# Safety_2019_V_3_0_Connectors.net
KiCad netlist of a schematic drawn in Altium Designer
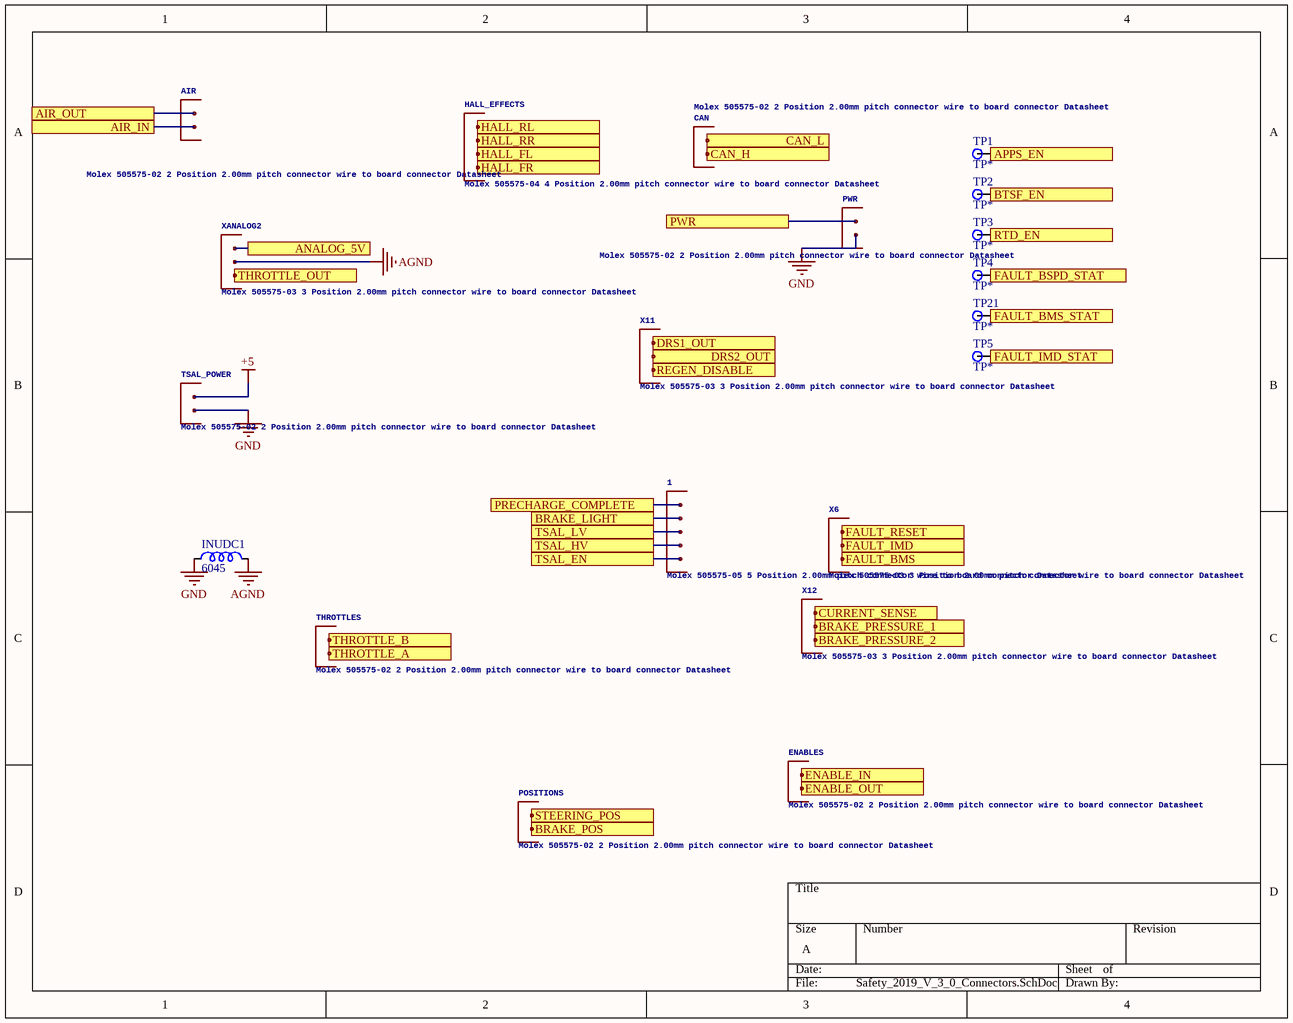
[diagram p0: Safety_2019_V_3_0_Connectors.SchDoc]

(export (version "E")
  (design (tool "Eeschema 10.0.6"))
  (components
    (comp (ref "1")
      (value "Molex 505575-05 5 Position 2.00mm pitch connector wire to board connector Datasheet")
      (footprint "505575-05")
      (fields (field (name "LIBRARYNAME") "MOLEX Micro-Lock"))
      (libsource (lib "MOLEX Micro-Lock") (part "505575-05"))
    )
    (comp (ref "AIR")
      (value "Molex 505575-02 2 Position 2.00mm pitch connector wire to board connector Datasheet")
      (footprint "505575-02")
      (fields (field (name "LIBRARYNAME") "MOLEX Micro-Lock"))
      (libsource (lib "MOLEX Micro-Lock") (part "505575-02"))
    )
    (comp (ref "CAN")
      (value "Molex 505575-02 2 Position 2.00mm pitch connector wire to board connector Datasheet")
      (footprint "505575-02")
      (fields (field (name "LIBRARYNAME") "MOLEX Micro-Lock"))
      (libsource (lib "MOLEX Micro-Lock") (part "505575-02"))
    )
    (comp (ref "ENABLES")
      (value "Molex 505575-02 2 Position 2.00mm pitch connector wire to board connector Datasheet")
      (footprint "505575-02")
      (fields (field (name "LIBRARYNAME") "MOLEX Micro-Lock"))
      (libsource (lib "MOLEX Micro-Lock") (part "505575-02"))
    )
    (comp (ref "HALL_EFFECTS")
      (value "Molex 505575-04 4 Position 2.00mm pitch connector wire to board connector Datasheet")
      (footprint "505575-04")
      (fields (field (name "LIBRARYNAME") "MOLEX Micro-Lock"))
      (libsource (lib "MOLEX Micro-Lock") (part "505575-04"))
    )
    (comp (ref "INUDC1")
      (value "6045")
      (footprint "IND-6045")
      (libsource (lib "ife19_Elec_Library") (part "IND-6045"))
    )
    (comp (ref "POSITIONS")
      (value "Molex 505575-02 2 Position 2.00mm pitch connector wire to board connector Datasheet")
      (footprint "505575-02")
      (fields (field (name "LIBRARYNAME") "MOLEX Micro-Lock"))
      (libsource (lib "MOLEX Micro-Lock") (part "505575-02"))
    )
    (comp (ref "PWR")
      (value "Molex 505575-02 2 Position 2.00mm pitch connector wire to board connector Datasheet")
      (footprint "505575-02")
      (fields (field (name "LIBRARYNAME") "MOLEX Micro-Lock"))
      (libsource (lib "MOLEX Micro-Lock") (part "505575-02"))
    )
    (comp (ref "THROTTLES")
      (value "Molex 505575-02 2 Position 2.00mm pitch connector wire to board connector Datasheet")
      (footprint "505575-02")
      (fields (field (name "LIBRARYNAME") "MOLEX Micro-Lock"))
      (libsource (lib "MOLEX Micro-Lock") (part "505575-02"))
    )
    (comp (ref "TP1")
      (value "TP*")
      (footprint "Testpoint")
      (libsource (lib "ife19_Elec_Library") (part "Testpoint"))
    )
    (comp (ref "TP2")
      (value "TP*")
      (footprint "Testpoint")
      (libsource (lib "ife19_Elec_Library") (part "Testpoint"))
    )
    (comp (ref "TP3")
      (value "TP*")
      (footprint "Testpoint")
      (libsource (lib "ife19_Elec_Library") (part "Testpoint"))
    )
    (comp (ref "TP4")
      (value "TP*")
      (footprint "Testpoint")
      (libsource (lib "ife19_Elec_Library") (part "Testpoint"))
    )
    (comp (ref "TP5")
      (value "TP*")
      (footprint "Testpoint")
      (libsource (lib "ife19_Elec_Library") (part "Testpoint"))
    )
    (comp (ref "TP21")
      (value "TP*")
      (footprint "Testpoint")
      (libsource (lib "ife19_Elec_Library") (part "Testpoint"))
    )
    (comp (ref "TSAL_POWER")
      (value "Molex 505575-02 2 Position 2.00mm pitch connector wire to board connector Datasheet")
      (footprint "505575-02")
      (fields (field (name "LIBRARYNAME") "MOLEX Micro-Lock"))
      (libsource (lib "MOLEX Micro-Lock") (part "505575-02"))
    )
    (comp (ref "X6")
      (value "Molex 505575-03 3 Position 2.00mm pitch connector wire to board connector Datasheet")
      (footprint "505575-03")
      (fields (field (name "LIBRARYNAME") "MOLEX Micro-Lock"))
      (libsource (lib "MOLEX Micro-Lock") (part "505575-03"))
    )
    (comp (ref "X11")
      (value "Molex 505575-03 3 Position 2.00mm pitch connector wire to board connector Datasheet")
      (footprint "505575-03")
      (fields (field (name "LIBRARYNAME") "MOLEX Micro-Lock"))
      (libsource (lib "MOLEX Micro-Lock") (part "505575-03"))
    )
    (comp (ref "X12")
      (value "Molex 505575-03 3 Position 2.00mm pitch connector wire to board connector Datasheet")
      (footprint "505575-03")
      (fields (field (name "LIBRARYNAME") "MOLEX Micro-Lock"))
      (libsource (lib "MOLEX Micro-Lock") (part "505575-03"))
    )
    (comp (ref "XANALOG2")
      (value "Molex 505575-03 3 Position 2.00mm pitch connector wire to board connector Datasheet")
      (footprint "505575-03")
      (fields (field (name "LIBRARYNAME") "MOLEX Micro-Lock"))
      (libsource (lib "MOLEX Micro-Lock") (part "505575-03"))
    )
  )
  (nets
    (net (code "1") (name "+5") (class "Default")
      (node (ref "TSAL_POWER") (pin "1") (pinfunction "1_1") (pintype "passive"))
    )
    (net (code "2") (name "/AIR_IN") (class "Default")
      (node (ref "AIR") (pin "2") (pinfunction "2_2") (pintype "passive"))
    )
    (net (code "3") (name "/AIR_OUT") (class "Default")
      (node (ref "AIR") (pin "1") (pinfunction "1_1") (pintype "passive"))
    )
    (net (code "4") (name "/ANALOG_5V") (class "Default")
      (node (ref "XANALOG2") (pin "1") (pinfunction "1_1") (pintype "passive"))
    )
    (net (code "5") (name "/APPS_EN") (class "Default")
      (node (ref "TP1") (pin "1") (pinfunction "1_1") (pintype "passive"))
    )
    (net (code "6") (name "/BRAKE_LIGHT") (class "Default")
      (node (ref "1") (pin "2") (pinfunction "2_2") (pintype "passive"))
    )
    (net (code "7") (name "/BRAKE_POS") (class "Default")
      (node (ref "POSITIONS") (pin "2") (pinfunction "2_2") (pintype "passive"))
    )
    (net (code "8") (name "/BRAKE_PRESSURE_1") (class "Default")
      (node (ref "X12") (pin "2") (pinfunction "2_2") (pintype "passive"))
    )
    (net (code "9") (name "/BRAKE_PRESSURE_2") (class "Default")
      (node (ref "X12") (pin "3") (pinfunction "3_3") (pintype "passive"))
    )
    (net (code "10") (name "/BTSF_EN") (class "Default")
      (node (ref "TP2") (pin "1") (pinfunction "1_1") (pintype "passive"))
    )
    (net (code "11") (name "/CAN_H") (class "Default")
      (node (ref "CAN") (pin "2") (pinfunction "2_2") (pintype "passive"))
    )
    (net (code "12") (name "/CAN_L") (class "Default")
      (node (ref "CAN") (pin "1") (pinfunction "1_1") (pintype "passive"))
    )
    (net (code "13") (name "/CURRENT_SENSE") (class "Default")
      (node (ref "X12") (pin "1") (pinfunction "1_1") (pintype "passive"))
    )
    (net (code "14") (name "/DRS1_OUT") (class "Default")
      (node (ref "X11") (pin "1") (pinfunction "1_1") (pintype "passive"))
    )
    (net (code "15") (name "/DRS2_OUT") (class "Default")
      (node (ref "X11") (pin "2") (pinfunction "2_2") (pintype "passive"))
    )
    (net (code "16") (name "/ENABLE_IN") (class "Default")
      (node (ref "ENABLES") (pin "1") (pinfunction "1_1") (pintype "passive"))
    )
    (net (code "17") (name "/ENABLE_OUT") (class "Default")
      (node (ref "ENABLES") (pin "2") (pinfunction "2_2") (pintype "passive"))
    )
    (net (code "18") (name "/FAULT_BMS") (class "Default")
      (node (ref "X6") (pin "3") (pinfunction "3_3") (pintype "passive"))
    )
    (net (code "19") (name "/FAULT_BMS_STAT") (class "Default")
      (node (ref "TP21") (pin "1") (pinfunction "1_1") (pintype "passive"))
    )
    (net (code "20") (name "/FAULT_BSPD_STAT") (class "Default")
      (node (ref "TP4") (pin "1") (pinfunction "1_1") (pintype "passive"))
    )
    (net (code "21") (name "/FAULT_IMD") (class "Default")
      (node (ref "X6") (pin "2") (pinfunction "2_2") (pintype "passive"))
    )
    (net (code "22") (name "/FAULT_IMD_STAT") (class "Default")
      (node (ref "TP5") (pin "1") (pinfunction "1_1") (pintype "passive"))
    )
    (net (code "23") (name "/FAULT_RESET") (class "Default")
      (node (ref "X6") (pin "1") (pinfunction "1_1") (pintype "passive"))
    )
    (net (code "24") (name "/HALL_FL") (class "Default")
      (node (ref "HALL_EFFECTS") (pin "3") (pinfunction "3_3") (pintype "passive"))
    )
    (net (code "25") (name "/HALL_FR") (class "Default")
      (node (ref "HALL_EFFECTS") (pin "4") (pinfunction "4_4") (pintype "passive"))
    )
    (net (code "26") (name "/HALL_RL") (class "Default")
      (node (ref "HALL_EFFECTS") (pin "1") (pinfunction "1_1") (pintype "passive"))
    )
    (net (code "27") (name "/HALL_RR") (class "Default")
      (node (ref "HALL_EFFECTS") (pin "2") (pinfunction "2_2") (pintype "passive"))
    )
    (net (code "28") (name "/PRECHARGE_COMPLETE") (class "Default")
      (node (ref "1") (pin "1") (pinfunction "1_1") (pintype "passive"))
    )
    (net (code "29") (name "/PWR") (class "Default")
      (node (ref "PWR") (pin "1") (pinfunction "1_1") (pintype "passive"))
    )
    (net (code "30") (name "/REGEN_DISABLE") (class "Default")
      (node (ref "X11") (pin "3") (pinfunction "3_3") (pintype "passive"))
    )
    (net (code "31") (name "/RTD_EN") (class "Default")
      (node (ref "TP3") (pin "1") (pinfunction "1_1") (pintype "passive"))
    )
    (net (code "32") (name "/STEERING_POS") (class "Default")
      (node (ref "POSITIONS") (pin "1") (pinfunction "1_1") (pintype "passive"))
    )
    (net (code "33") (name "/THROTTLE_A") (class "Default")
      (node (ref "THROTTLES") (pin "2") (pinfunction "2_2") (pintype "passive"))
    )
    (net (code "34") (name "/THROTTLE_B") (class "Default")
      (node (ref "THROTTLES") (pin "1") (pinfunction "1_1") (pintype "passive"))
    )
    (net (code "35") (name "/THROTTLE_OUT") (class "Default")
      (node (ref "XANALOG2") (pin "3") (pinfunction "3_3") (pintype "passive"))
    )
    (net (code "36") (name "/TSAL_EN") (class "Default")
      (node (ref "1") (pin "5") (pinfunction "5_5") (pintype "passive"))
    )
    (net (code "37") (name "/TSAL_HV") (class "Default")
      (node (ref "1") (pin "4") (pinfunction "4_4") (pintype "passive"))
    )
    (net (code "38") (name "/TSAL_LV") (class "Default")
      (node (ref "1") (pin "3") (pinfunction "3_3") (pintype "passive"))
    )
    (net (code "39") (name "AGND") (class "Default")
      (node (ref "INUDC1") (pin "2") (pinfunction "2_2") (pintype "passive"))
      (node (ref "XANALOG2") (pin "2") (pinfunction "2_2") (pintype "passive"))
    )
    (net (code "40") (name "GND") (class "Default")
      (node (ref "INUDC1") (pin "1") (pinfunction "1_1") (pintype "passive"))
      (node (ref "PWR") (pin "2") (pinfunction "2_2") (pintype "passive"))
      (node (ref "TSAL_POWER") (pin "2") (pinfunction "2_2") (pintype "passive"))
    )
  )
)
